# Fri3D_2020_ESP32.net
KiCad netlist of a schematic drawn in Altium Designer
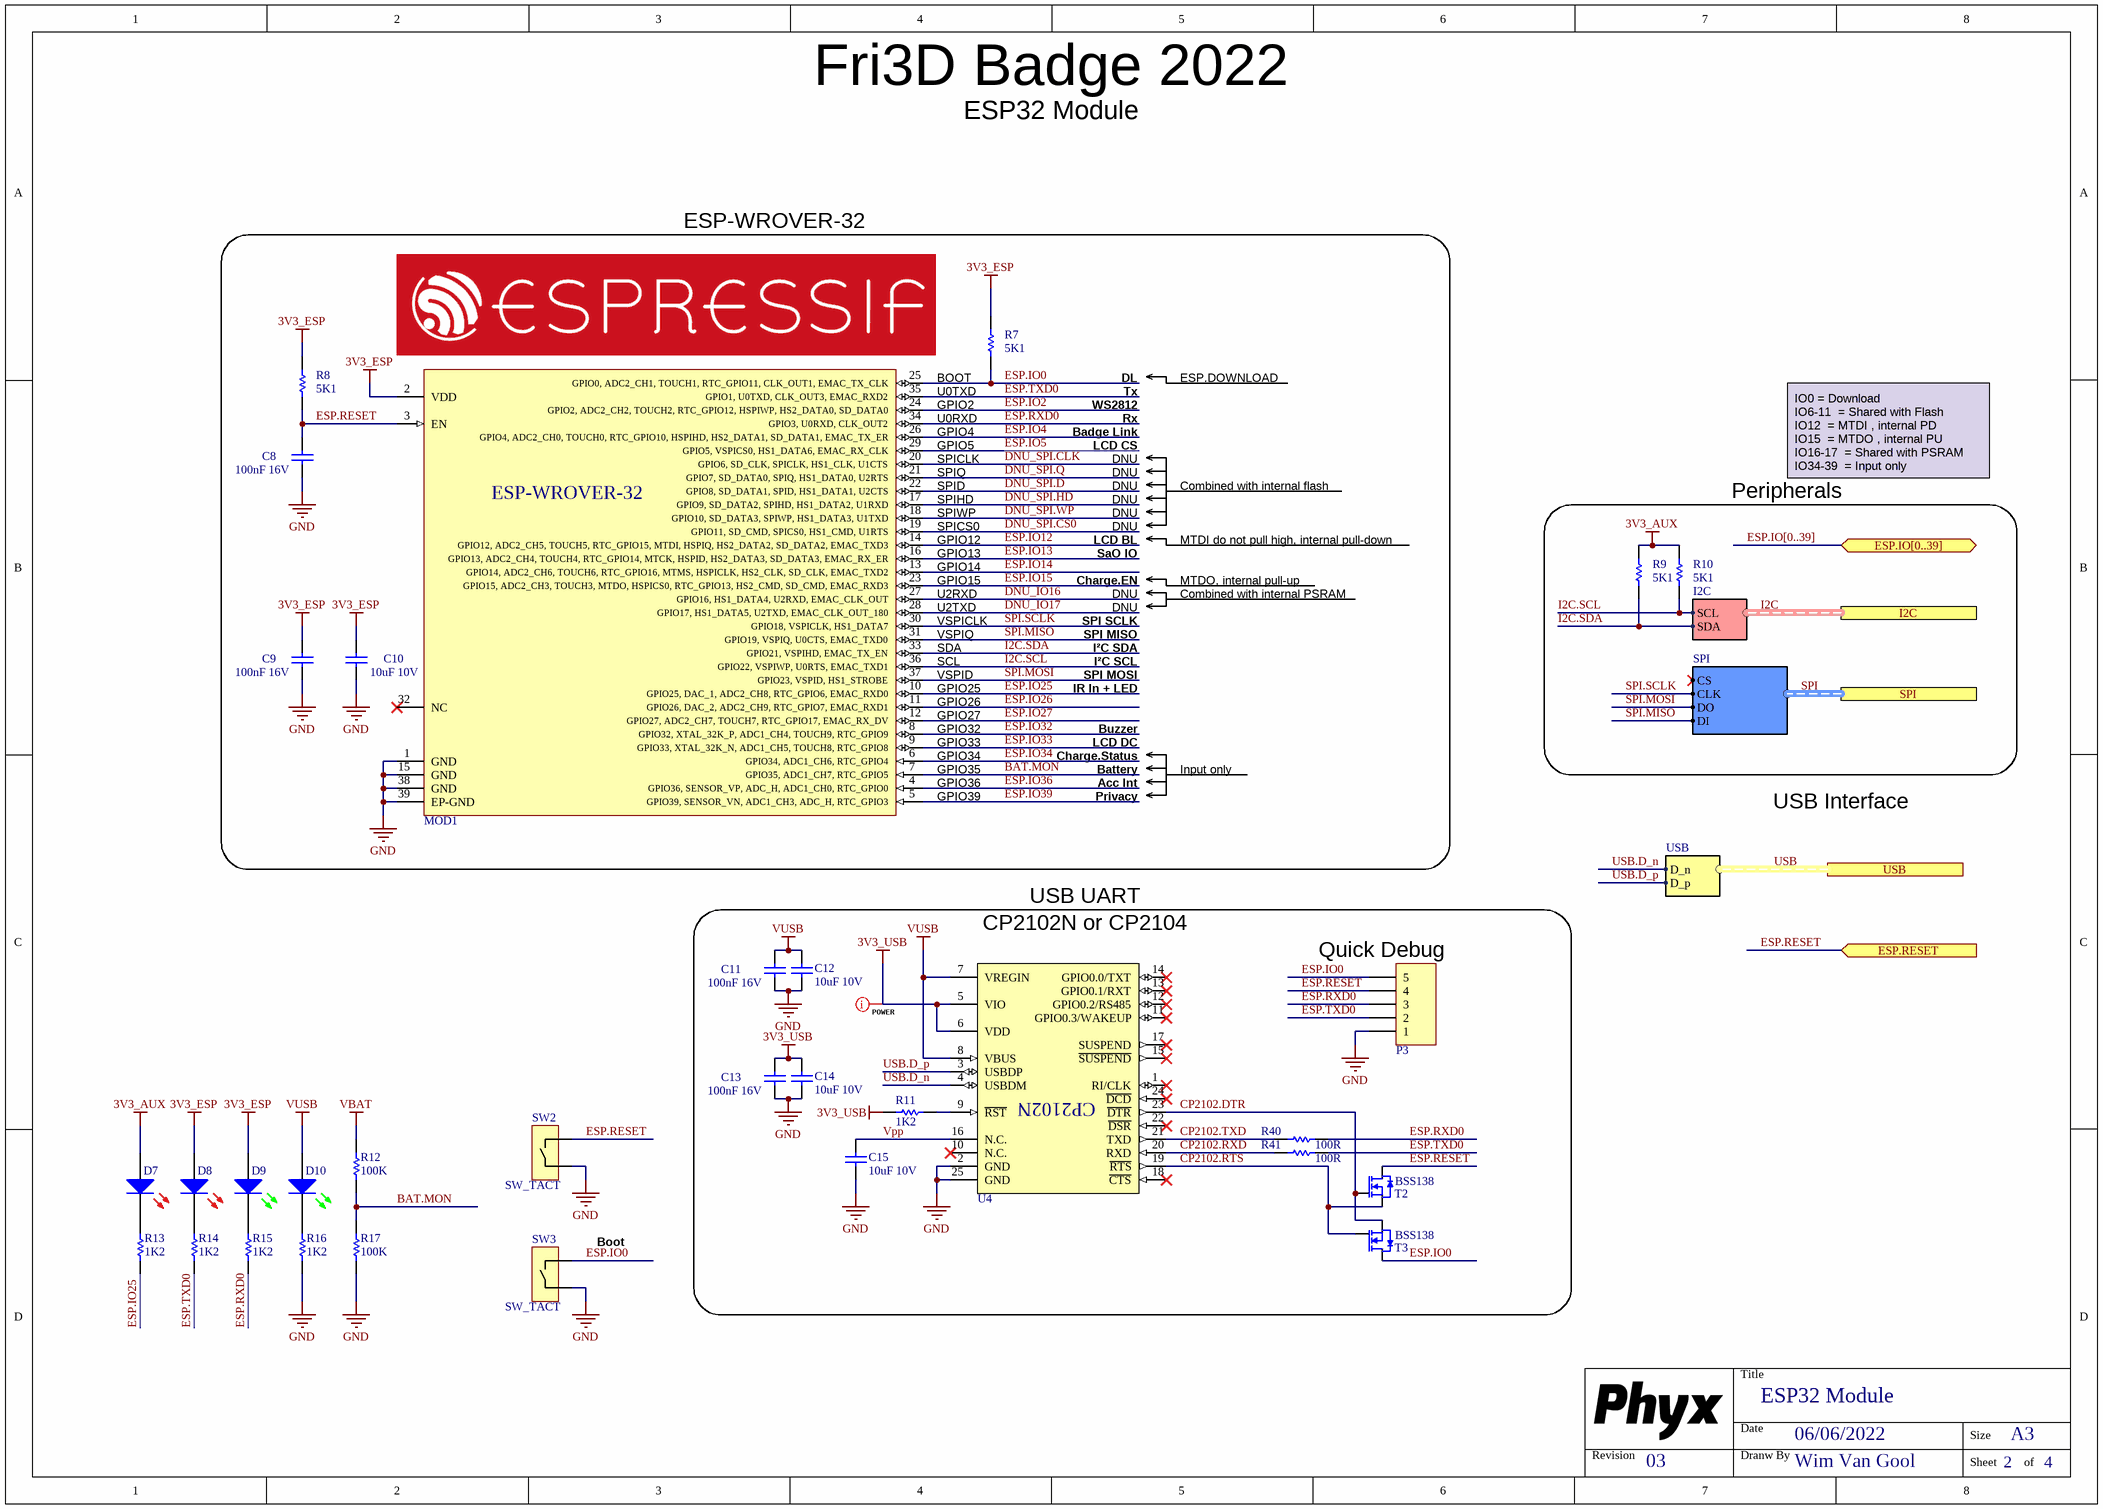
[diagram p0: Fri3D_2020_ESP32.SchDoc]

(export (version "E")
  (design (tool "Eeschema 10.0.6"))
  (components
    (comp (ref "C8")
      (value "100nF 16V")
      (footprint "C0603_N")
      (description "Capacitor Ceramic")
      (libsource (lib "Phyx_Components") (part "CAP_CERAMIC"))
    )
    (comp (ref "C9")
      (value "100nF 16V")
      (footprint "C0603_N")
      (description "Capacitor Ceramic")
      (libsource (lib "Phyx_Components") (part "CAP_CERAMIC"))
    )
    (comp (ref "C10")
      (value "10uF 10V")
      (footprint "C0805_N")
      (description "Capacitor Ceramic")
      (fields (field (name "Comment") "CAP_CERAMIC"))
      (libsource (lib "Phyx_Components") (part "CAP_CERAMIC"))
    )
    (comp (ref "C11")
      (value "100nF 16V")
      (footprint "C0603_N")
      (description "Capacitor Ceramic")
      (libsource (lib "Phyx_Components") (part "CAP_CERAMIC"))
    )
    (comp (ref "C12")
      (value "10uF 10V")
      (footprint "C0805_N")
      (description "Capacitor Ceramic")
      (fields (field (name "Comment") "CAP_CERAMIC"))
      (libsource (lib "Phyx_Components") (part "CAP_CERAMIC"))
    )
    (comp (ref "C13")
      (value "100nF 16V")
      (footprint "C0603_N")
      (description "Capacitor Ceramic")
      (libsource (lib "Phyx_Components") (part "CAP_CERAMIC"))
    )
    (comp (ref "C14")
      (value "10uF 10V")
      (footprint "C0805_N")
      (description "Capacitor Ceramic")
      (fields (field (name "Comment") "CAP_CERAMIC"))
      (libsource (lib "Phyx_Components") (part "CAP_CERAMIC"))
    )
    (comp (ref "C15")
      (value "10uF 10V")
      (footprint "C0805_N")
      (description "Capacitor Ceramic")
      (fields (field (name "Comment") "CAP_CERAMIC"))
      (libsource (lib "Phyx_Components") (part "CAP_CERAMIC"))
    )
    (comp (ref "D7")
      (value "Default 0805 Red LED")
      (footprint "LED_0805_RD")
      (description "=Description")
      (libsource (lib "Phyx_Components") (part "LED_RED"))
    )
    (comp (ref "D8")
      (value "Default 0805 Red LED")
      (footprint "LED_0805_RD")
      (description "=Description")
      (libsource (lib "Phyx_Components") (part "LED_RED"))
    )
    (comp (ref "D9")
      (value "Default 0805 Green LED")
      (footprint "LED_0805_GR")
      (description "=Description")
      (libsource (lib "Phyx_Components") (part "LED_GREEN"))
    )
    (comp (ref "D10")
      (value "Default 0805 Green LED")
      (footprint "LED_0805_GR")
      (description "=Description")
      (libsource (lib "Phyx_Components") (part "LED_GREEN"))
    )
    (comp (ref "MOD1")
      (value "ESP-32 based ESP-WROVER-32")
      (footprint "ESP-WROVER-32")
      (description "WiFi # MOD ESP-WROVER-32")
      (libsource (lib "Phyx_Components") (part "ESP-WROVER-32"))
    )
    (comp (ref "P3")
      (value "Header 1.0mm RA Shrouded 5")
      (footprint "WE_665105131822")
      (libsource (lib "Phyx_Components") (part "Header 5"))
    )
    (comp (ref "R7")
      (value "5K1")
      (footprint "R0603_N")
      (fields (field (name "Comment") "RESISTOR"))
      (libsource (lib "Phyx_Components") (part "RESISTOR"))
    )
    (comp (ref "R8")
      (value "5K1")
      (footprint "R0603_N")
      (fields (field (name "Comment") "RESISTOR"))
      (libsource (lib "Phyx_Components") (part "RESISTOR"))
    )
    (comp (ref "R9")
      (value "5K1")
      (footprint "R0603_N")
      (fields (field (name "Comment") "RESISTOR"))
      (libsource (lib "Phyx_Components") (part "RESISTOR"))
    )
    (comp (ref "R10")
      (value "5K1")
      (footprint "R0603_N")
      (fields (field (name "Comment") "RESISTOR"))
      (libsource (lib "Phyx_Components") (part "RESISTOR"))
    )
    (comp (ref "R11")
      (value "1K2")
      (footprint "R0603_N")
      (fields (field (name "Comment") "RESISTOR"))
      (libsource (lib "Phyx_Components") (part "RESISTOR"))
    )
    (comp (ref "R12")
      (value "100K")
      (footprint "R0603_N")
      (fields (field (name "Comment") "RESISTOR"))
      (libsource (lib "Phyx_Components") (part "RESISTOR"))
    )
    (comp (ref "R13")
      (value "1K2")
      (footprint "R0603_N")
      (fields (field (name "Comment") "RESISTOR"))
      (libsource (lib "Phyx_Components") (part "RESISTOR"))
    )
    (comp (ref "R14")
      (value "1K2")
      (footprint "R0603_N")
      (fields (field (name "Comment") "RESISTOR"))
      (libsource (lib "Phyx_Components") (part "RESISTOR"))
    )
    (comp (ref "R15")
      (value "1K2")
      (footprint "R0603_N")
      (fields (field (name "Comment") "RESISTOR"))
      (libsource (lib "Phyx_Components") (part "RESISTOR"))
    )
    (comp (ref "R16")
      (value "1K2")
      (footprint "R0603_N")
      (fields (field (name "Comment") "RESISTOR"))
      (libsource (lib "Phyx_Components") (part "RESISTOR"))
    )
    (comp (ref "R17")
      (value "100K")
      (footprint "R0603_N")
      (fields (field (name "Comment") "RESISTOR"))
      (libsource (lib "Phyx_Components") (part "RESISTOR"))
    )
    (comp (ref "R40")
      (value "100R")
      (footprint "R0603_N")
      (fields (field (name "Comment") "RESISTOR"))
      (libsource (lib "Phyx_Components") (part "RESISTOR"))
    )
    (comp (ref "R41")
      (value "100R")
      (footprint "R0603_N")
      (fields (field (name "Comment") "RESISTOR"))
      (libsource (lib "Phyx_Components") (part "RESISTOR"))
    )
    (comp (ref "SW2")
      (value "SW_TACT")
      (footprint "WE_430181038816")
      (libsource (lib "Phyx_Components") (part "SW_TACT"))
    )
    (comp (ref "SW3")
      (value "SW_TACT")
      (footprint "WE_430181038816")
      (libsource (lib "Phyx_Components") (part "SW_TACT"))
    )
    (comp (ref "T2")
      (value "BSS138")
      (footprint "SOT23-3")
      (fields (field (name "Comment") "0.2A N-Ch MOSFET Vgs 3.2"))
      (libsource (lib "Phyx_Components") (part "N_MOSFET_GSD"))
    )
    (comp (ref "T3")
      (value "BSS138")
      (footprint "SOT23-3")
      (fields (field (name "Comment") "0.2A N-Ch MOSFET Vgs 3.2"))
      (libsource (lib "Phyx_Components") (part "N_MOSFET_GSD"))
    )
    (comp (ref "U4")
      (value "USB to UART 3.3-5V")
      (footprint "QFN_24")
      (description "=Description")
      (libsource (lib "Phyx_Components") (part "CP2102N_QFN24"))
    )
  )
  (nets
    (net (code "28") (name "/BAT.MON") (class "Default")
      (node (ref "MOD1") (pin "7") (pinfunction "GPIO35,_ADC1_CH7,_RTC_GPIO5_7") (pintype "input"))
      (node (ref "R12") (pin "2") (pinfunction "2_2") (pintype "passive"))
      (node (ref "R17") (pin "1") (pinfunction "1_1") (pintype "passive"))
    )
    (net (code "29") (name "/CP2102.DTR") (class "Default")
      (node (ref "T2") (pin "1") (pinfunction "G_1") (pintype "passive"))
      (node (ref "T3") (pin "2") (pinfunction "S_2") (pintype "passive"))
      (node (ref "U4") (pin "23") (pinfunction "~{DTR}_23") (pintype "output"))
    )
    (net (code "30") (name "/CP2102.RTS") (class "Default")
      (node (ref "T2") (pin "2") (pinfunction "S_2") (pintype "passive"))
      (node (ref "T3") (pin "1") (pinfunction "G_1") (pintype "passive"))
      (node (ref "U4") (pin "19") (pinfunction "~{RTS}_19") (pintype "output"))
    )
    (net (code "31") (name "/CP2102.RXD") (class "Default")
      (node (ref "R41") (pin "1") (pinfunction "1_1") (pintype "passive"))
      (node (ref "U4") (pin "20") (pinfunction "RXD_20") (pintype "input"))
    )
    (net (code "32") (name "/CP2102.TXD") (class "Default")
      (node (ref "R40") (pin "1") (pinfunction "1_1") (pintype "passive"))
      (node (ref "U4") (pin "21") (pinfunction "TXD_21") (pintype "output"))
    )
    (net (code "33") (name "/DNU_IO16") (class "Default")
      (node (ref "MOD1") (pin "27") (pinfunction "GPIO16,_HS1_DATA4,_U2RXD,_EMAC_CLK_OUT_27") (pintype "bidirectional"))
    )
    (net (code "34") (name "/DNU_IO17") (class "Default")
      (node (ref "MOD1") (pin "28") (pinfunction "GPIO17,_HS1_DATA5,_U2TXD,_EMAC_CLK_OUT_180_28") (pintype "bidirectional"))
    )
    (net (code "35") (name "/DNU_SPI.CLK") (class "Default")
      (node (ref "MOD1") (pin "20") (pinfunction "GPIO6,_SD_CLK,_SPICLK,_HS1_CLK,_U1CTS_20") (pintype "bidirectional"))
    )
    (net (code "36") (name "/DNU_SPI.CS0") (class "Default")
      (node (ref "MOD1") (pin "19") (pinfunction "GPIO11,_SD_CMD,_SPICS0,_HS1_CMD,_U1RTS_19") (pintype "bidirectional"))
    )
    (net (code "37") (name "/DNU_SPI.D") (class "Default")
      (node (ref "MOD1") (pin "22") (pinfunction "GPIO8,_SD_DATA1,_SPID,_HS1_DATA1,_U2CTS_22") (pintype "bidirectional"))
    )
    (net (code "38") (name "/DNU_SPI.HD") (class "Default")
      (node (ref "MOD1") (pin "17") (pinfunction "GPIO9,_SD_DATA2,_SPIHD,_HS1_DATA2,_U1RXD_17") (pintype "bidirectional"))
    )
    (net (code "39") (name "/DNU_SPI.Q") (class "Default")
      (node (ref "MOD1") (pin "21") (pinfunction "GPIO7,_SD_DATA0,_SPIQ,_HS1_DATA0,_U2RTS_21") (pintype "bidirectional"))
    )
    (net (code "40") (name "/DNU_SPI.WP") (class "Default")
      (node (ref "MOD1") (pin "18") (pinfunction "GPIO10,_SD_DATA3,_SPIWP,_HS1_DATA3,_U1TXD_18") (pintype "bidirectional"))
    )
    (net (code "41") (name "/ESP.IO0") (class "Default")
      (node (ref "MOD1") (pin "25") (pinfunction "GPIO0,_ADC2_CH1,_TOUCH1,_RTC_GPIO11,_CLK_OUT1,_EMAC_TX_CLK_25") (pintype "bidirectional"))
      (node (ref "P3") (pin "5") (pinfunction "5_5") (pintype "passive"))
      (node (ref "R7") (pin "2") (pinfunction "2_2") (pintype "passive"))
      (node (ref "SW3") (pin "1") (pinfunction "1_1") (pintype "passive"))
      (node (ref "T3") (pin "3") (pinfunction "D_3") (pintype "passive"))
    )
    (net (code "42") (name "/ESP.IO2") (class "Default")
      (node (ref "MOD1") (pin "24") (pinfunction "GPIO2,_ADC2_CH2,_TOUCH2,_RTC_GPIO12,_HSPIWP,_HS2_DATA0,_SD_DATA0_24") (pintype "bidirectional"))
    )
    (net (code "43") (name "/ESP.IO4") (class "Default")
      (node (ref "MOD1") (pin "26") (pinfunction "GPIO4,_ADC2_CH0,_TOUCH0,_RTC_GPIO10,_HSPIHD,_HS2_DATA1,_SD_DATA1,_EMAC_TX_ER_26") (pintype "bidirectional"))
    )
    (net (code "44") (name "/ESP.IO5") (class "Default")
      (node (ref "MOD1") (pin "29") (pinfunction "GPIO5,_VSPICS0,_HS1_DATA6,_EMAC_RX_CLK_29") (pintype "bidirectional"))
    )
    (net (code "45") (name "/ESP.IO12") (class "Default")
      (node (ref "MOD1") (pin "14") (pinfunction "GPIO12,_ADC2_CH5,_TOUCH5,_RTC_GPIO15,_MTDI,_HSPIQ,_HS2_DATA2,_SD_DATA2,_EMAC_TXD3_14") (pintype "bidirectional"))
    )
    (net (code "46") (name "/ESP.IO13") (class "Default")
      (node (ref "MOD1") (pin "16") (pinfunction "GPIO13,_ADC2_CH4,_TOUCH4,_RTC_GPIO14,_MTCK,_HSPID,_HS2_DATA3,_SD_DATA3,_EMAC_RX_ER_16") (pintype "bidirectional"))
    )
    (net (code "47") (name "/ESP.IO14") (class "Default")
      (node (ref "MOD1") (pin "13") (pinfunction "GPIO14,_ADC2_CH6,_TOUCH6,_RTC_GPIO16,_MTMS,_HSPICLK,_HS2_CLK,_SD_CLK,_EMAC_TXD2_13") (pintype "bidirectional"))
    )
    (net (code "48") (name "/ESP.IO15") (class "Default")
      (node (ref "MOD1") (pin "23") (pinfunction "GPIO15,_ADC2_CH3,_TOUCH3,_MTDO,_HSPICS0,_RTC_GPIO13,_HS2_CMD,_SD_CMD,_EMAC_RXD3_23") (pintype "bidirectional"))
    )
    (net (code "49") (name "/ESP.IO25") (class "Default")
      (node (ref "MOD1") (pin "10") (pinfunction "GPIO25,_DAC_1,_ADC2_CH8,_RTC_GPIO6,_EMAC_RXD0_10") (pintype "bidirectional"))
      (node (ref "R13") (pin "2") (pinfunction "2_2") (pintype "passive"))
    )
    (net (code "50") (name "/ESP.IO26") (class "Default")
      (node (ref "MOD1") (pin "11") (pinfunction "GPIO26,_DAC_2,_ADC2_CH9,_RTC_GPIO7,_EMAC_RXD1_11") (pintype "bidirectional"))
    )
    (net (code "51") (name "/ESP.IO27") (class "Default")
      (node (ref "MOD1") (pin "12") (pinfunction "GPIO27,_ADC2_CH7,_TOUCH7,_RTC_GPIO17,_EMAC_RX_DV_12") (pintype "bidirectional"))
    )
    (net (code "52") (name "/ESP.IO32") (class "Default")
      (node (ref "MOD1") (pin "8") (pinfunction "GPIO32,_XTAL_32K_P,_ADC1_CH4,_TOUCH9,_RTC_GPIO9_8") (pintype "bidirectional"))
    )
    (net (code "53") (name "/ESP.IO33") (class "Default")
      (node (ref "MOD1") (pin "9") (pinfunction "GPIO33,_XTAL_32K_N,_ADC1_CH5,_TOUCH8,_RTC_GPIO8_9") (pintype "bidirectional"))
    )
    (net (code "54") (name "/ESP.IO34") (class "Default")
      (node (ref "MOD1") (pin "6") (pinfunction "GPIO34,_ADC1_CH6,_RTC_GPIO4_6") (pintype "input"))
    )
    (net (code "55") (name "/ESP.IO36") (class "Default")
      (node (ref "MOD1") (pin "4") (pinfunction "GPIO36,_SENSOR_VP,_ADC_H,_ADC1_CH0,_RTC_GPIO0_4") (pintype "input"))
    )
    (net (code "56") (name "/ESP.IO39") (class "Default")
      (node (ref "MOD1") (pin "5") (pinfunction "GPIO39,_SENSOR_VN,_ADC1_CH3,_ADC_H,_RTC_GPIO3_5") (pintype "input"))
    )
    (net (code "58") (name "/ESP.RESET") (class "Default")
      (node (ref "C8") (pin "1") (pinfunction "1_1") (pintype "passive"))
      (node (ref "MOD1") (pin "3") (pinfunction "EN_3") (pintype "input"))
      (node (ref "P3") (pin "4") (pinfunction "4_4") (pintype "passive"))
      (node (ref "R8") (pin "2") (pinfunction "2_2") (pintype "passive"))
      (node (ref "SW2") (pin "1") (pinfunction "1_1") (pintype "passive"))
      (node (ref "T2") (pin "3") (pinfunction "D_3") (pintype "passive"))
    )
    (net (code "59") (name "/ESP.RXD0") (class "Default")
      (node (ref "MOD1") (pin "34") (pinfunction "GPIO3,_U0RXD,_CLK_OUT2_34") (pintype "bidirectional"))
      (node (ref "P3") (pin "3") (pinfunction "3_3") (pintype "passive"))
      (node (ref "R15") (pin "2") (pinfunction "2_2") (pintype "passive"))
      (node (ref "R40") (pin "2") (pinfunction "2_2") (pintype "passive"))
    )
    (net (code "60") (name "/ESP.TXD0") (class "Default")
      (node (ref "MOD1") (pin "35") (pinfunction "GPIO1,_U0TXD,_CLK_OUT3,_EMAC_RXD2_35") (pintype "bidirectional"))
      (node (ref "P3") (pin "2") (pinfunction "2_2") (pintype "passive"))
      (node (ref "R14") (pin "2") (pinfunction "2_2") (pintype "passive"))
      (node (ref "R41") (pin "2") (pinfunction "2_2") (pintype "passive"))
    )
    (net (code "61") (name "/I2C.SCL") (class "Default")
      (node (ref "MOD1") (pin "36") (pinfunction "GPIO22,_VSPIWP,_U0RTS,_EMAC_TXD1_36") (pintype "bidirectional"))
      (node (ref "R10") (pin "2") (pinfunction "2_2") (pintype "passive"))
    )
    (net (code "62") (name "/I2C.SDA") (class "Default")
      (node (ref "MOD1") (pin "33") (pinfunction "GPIO21,_VSPIHD,_EMAC_TX_EN_33") (pintype "bidirectional"))
      (node (ref "R9") (pin "2") (pinfunction "2_2") (pintype "passive"))
    )
    (net (code "64") (name "/SPI.MISO") (class "Default")
      (node (ref "MOD1") (pin "31") (pinfunction "GPIO19,_VSPIQ,_U0CTS,_EMAC_TXD0_31") (pintype "bidirectional"))
    )
    (net (code "65") (name "/SPI.MOSI") (class "Default")
      (node (ref "MOD1") (pin "37") (pinfunction "GPIO23,_VSPID,_HS1_STROBE_37") (pintype "bidirectional"))
    )
    (net (code "66") (name "/SPI.SCLK") (class "Default")
      (node (ref "MOD1") (pin "30") (pinfunction "GPIO18,_VSPICLK,_HS1_DATA7_30") (pintype "bidirectional"))
    )
    (net (code "68") (name "/USB.D_n") (class "Default")
      (node (ref "U4") (pin "4") (pinfunction "USBDM_4") (pintype "bidirectional"))
    )
    (net (code "69") (name "/USB.D_p") (class "Default")
      (node (ref "U4") (pin "3") (pinfunction "USBDP_3") (pintype "bidirectional"))
    )
    (net (code "71") (name "/Vpp") (class "Default")
      (node (ref "C15") (pin "2") (pinfunction "2_2") (pintype "passive"))
      (node (ref "U4") (pin "16") (pinfunction "N.C._16") (pintype "passive"))
    )
    (net (code "72") (name "3V3_AUX") (class "Default")
      (node (ref "D7") (pin "1") (pinfunction "A_1") (pintype "passive"))
      (node (ref "R10") (pin "1") (pinfunction "1_1") (pintype "passive"))
      (node (ref "R9") (pin "1") (pinfunction "1_1") (pintype "passive"))
    )
    (net (code "73") (name "3V3_ESP") (class "Default")
      (node (ref "C10") (pin "1") (pinfunction "1_1") (pintype "passive"))
      (node (ref "C9") (pin "1") (pinfunction "1_1") (pintype "passive"))
      (node (ref "D8") (pin "1") (pinfunction "A_1") (pintype "passive"))
      (node (ref "D9") (pin "1") (pinfunction "A_1") (pintype "passive"))
      (node (ref "MOD1") (pin "2") (pinfunction "VDD_2") (pintype "power_in"))
      (node (ref "R7") (pin "1") (pinfunction "1_1") (pintype "passive"))
      (node (ref "R8") (pin "1") (pinfunction "1_1") (pintype "passive"))
    )
    (net (code "74") (name "3V3_USB") (class "Default")
      (node (ref "C13") (pin "1") (pinfunction "1_1") (pintype "passive"))
      (node (ref "C14") (pin "2") (pinfunction "2_2") (pintype "passive"))
      (node (ref "R11") (pin "1") (pinfunction "1_1") (pintype "passive"))
      (node (ref "U4") (pin "5") (pinfunction "VIO_5") (pintype "power_in"))
      (node (ref "U4") (pin "6") (pinfunction "VDD_6") (pintype "power_in"))
    )
    (net (code "75") (name "GND") (class "Default")
      (node (ref "C10") (pin "2") (pinfunction "2_2") (pintype "passive"))
      (node (ref "C11") (pin "2") (pinfunction "2_2") (pintype "passive"))
      (node (ref "C12") (pin "1") (pinfunction "1_1") (pintype "passive"))
      (node (ref "C13") (pin "2") (pinfunction "2_2") (pintype "passive"))
      (node (ref "C14") (pin "1") (pinfunction "1_1") (pintype "passive"))
      (node (ref "C15") (pin "1") (pinfunction "1_1") (pintype "passive"))
      (node (ref "C8") (pin "2") (pinfunction "2_2") (pintype "passive"))
      (node (ref "C9") (pin "2") (pinfunction "2_2") (pintype "passive"))
      (node (ref "MOD1") (pin "1") (pinfunction "GND_1") (pintype "power_in"))
      (node (ref "MOD1") (pin "15") (pinfunction "GND_15") (pintype "power_in"))
      (node (ref "MOD1") (pin "38") (pinfunction "GND_38") (pintype "power_in"))
      (node (ref "MOD1") (pin "39") (pinfunction "EP-GND_39") (pintype "power_in"))
      (node (ref "P3") (pin "1") (pinfunction "1_1") (pintype "passive"))
      (node (ref "R16") (pin "2") (pinfunction "2_2") (pintype "passive"))
      (node (ref "R17") (pin "2") (pinfunction "2_2") (pintype "passive"))
      (node (ref "SW2") (pin "2") (pinfunction "2_2") (pintype "passive"))
      (node (ref "SW3") (pin "2") (pinfunction "2_2") (pintype "passive"))
      (node (ref "U4") (pin "2") (pinfunction "GND_2") (pintype "power_in"))
      (node (ref "U4") (pin "25") (pinfunction "GND_25") (pintype "power_in"))
    )
    (net (code "76") (name "Net-(D7-K)") (class "Default")
      (node (ref "D7") (pin "2") (pinfunction "K_2") (pintype "passive"))
      (node (ref "R13") (pin "1") (pinfunction "1_1") (pintype "passive"))
    )
    (net (code "77") (name "Net-(D8-K)") (class "Default")
      (node (ref "D8") (pin "2") (pinfunction "K_2") (pintype "passive"))
      (node (ref "R14") (pin "1") (pinfunction "1_1") (pintype "passive"))
    )
    (net (code "78") (name "Net-(D9-K)") (class "Default")
      (node (ref "D9") (pin "2") (pinfunction "K_2") (pintype "passive"))
      (node (ref "R15") (pin "1") (pinfunction "1_1") (pintype "passive"))
    )
    (net (code "79") (name "Net-(D10-K)") (class "Default")
      (node (ref "D10") (pin "2") (pinfunction "K_2") (pintype "passive"))
      (node (ref "R16") (pin "1") (pinfunction "1_1") (pintype "passive"))
    )
    (net (code "80") (name "Net-(U4-~{RST})") (class "Default")
      (node (ref "R11") (pin "2") (pinfunction "2_2") (pintype "passive"))
      (node (ref "U4") (pin "9") (pinfunction "~{RST}_9") (pintype "input"))
    )
    (net (code "81") (name "VBAT") (class "Default")
      (node (ref "R12") (pin "1") (pinfunction "1_1") (pintype "passive"))
    )
    (net (code "82") (name "VUSB") (class "Default")
      (node (ref "C11") (pin "1") (pinfunction "1_1") (pintype "passive"))
      (node (ref "C12") (pin "2") (pinfunction "2_2") (pintype "passive"))
      (node (ref "D10") (pin "1") (pinfunction "A_1") (pintype "passive"))
      (node (ref "U4") (pin "7") (pinfunction "VREGIN_7") (pintype "power_in"))
      (node (ref "U4") (pin "8") (pinfunction "VBUS_8") (pintype "input"))
    )
    (net (code "83") (name "unconnected-(MOD1-NC-Pad32)") (class "Default")
      (node (ref "MOD1") (pin "32") (pinfunction "NC_32") (pintype "passive+no_connect"))
    )
    (net (code "84") (name "unconnected-(U4-GPIO0.0{slash}TXT-Pad14)") (class "Default")
      (node (ref "U4") (pin "14") (pinfunction "GPIO0.0/TXT_14") (pintype "bidirectional+no_connect"))
    )
    (net (code "85") (name "unconnected-(U4-GPIO0.1{slash}RXT-Pad13)") (class "Default")
      (node (ref "U4") (pin "13") (pinfunction "GPIO0.1/RXT_13") (pintype "bidirectional+no_connect"))
    )
    (net (code "86") (name "unconnected-(U4-GPIO0.2{slash}RS485-Pad12)") (class "Default")
      (node (ref "U4") (pin "12") (pinfunction "GPIO0.2/RS485_12") (pintype "bidirectional+no_connect"))
    )
    (net (code "87") (name "unconnected-(U4-GPIO0.3{slash}WAKEUP-Pad11)") (class "Default")
      (node (ref "U4") (pin "11") (pinfunction "GPIO0.3/WAKEUP_11") (pintype "bidirectional+no_connect"))
    )
    (net (code "88") (name "unconnected-(U4-N.C.-Pad10)") (class "Default")
      (node (ref "U4") (pin "10") (pinfunction "N.C._10") (pintype "passive+no_connect"))
    )
    (net (code "89") (name "unconnected-(U4-RI{slash}CLK-Pad1)") (class "Default")
      (node (ref "U4") (pin "1") (pinfunction "RI/CLK_1") (pintype "bidirectional+no_connect"))
    )
    (net (code "90") (name "unconnected-(U4-SUSPEND-Pad17)") (class "Default")
      (node (ref "U4") (pin "17") (pinfunction "SUSPEND_17") (pintype "output+no_connect"))
    )
    (net (code "91") (name "unconnected-(U4-~{CTS}-Pad18)") (class "Default")
      (node (ref "U4") (pin "18") (pinfunction "~{CTS}_18") (pintype "input+no_connect"))
    )
    (net (code "92") (name "unconnected-(U4-~{DCD}-Pad24)") (class "Default")
      (node (ref "U4") (pin "24") (pinfunction "~{DCD}_24") (pintype "input+no_connect"))
    )
    (net (code "93") (name "unconnected-(U4-~{DSR}-Pad22)") (class "Default")
      (node (ref "U4") (pin "22") (pinfunction "~{DSR}_22") (pintype "input+no_connect"))
    )
    (net (code "94") (name "unconnected-(U4-~{SUSPEND}-Pad15)") (class "Default")
      (node (ref "U4") (pin "15") (pinfunction "~{SUSPEND}_15") (pintype "output+no_connect"))
    )
  )
)
